# Driver.net
KiCad netlist of a schematic drawn in Altium Designer
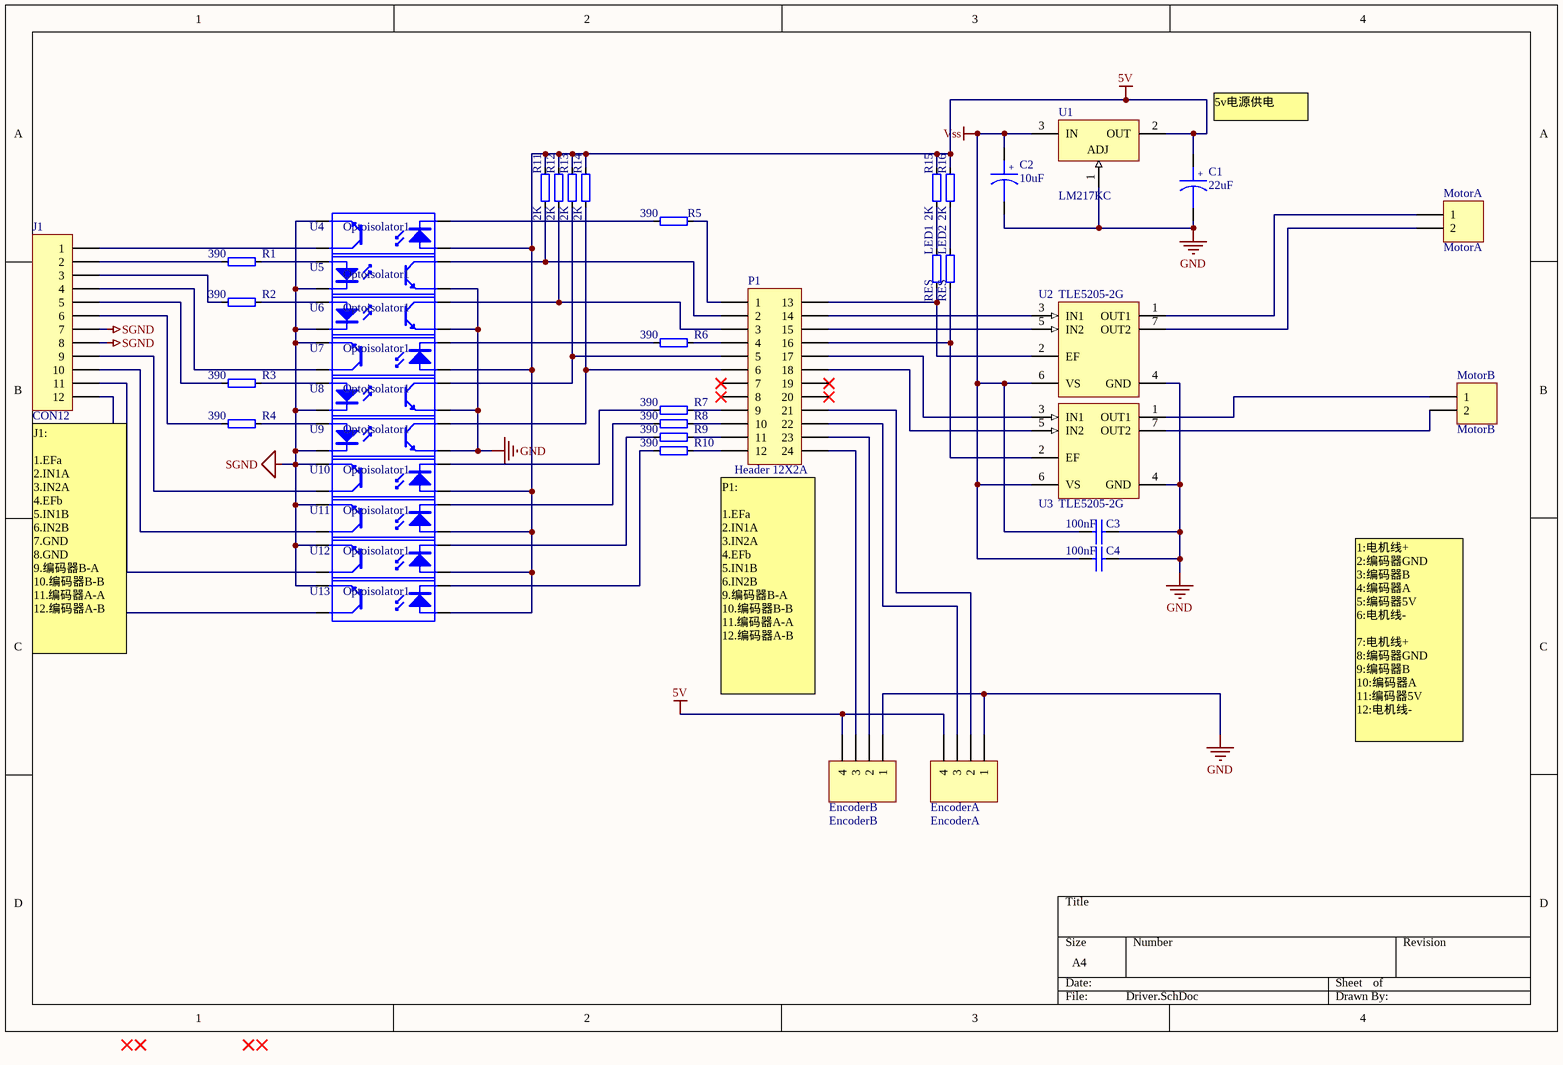
[diagram p0: Driver.SchDoc]

(export (version "E")
  (design (tool "Eeschema 10.0.6"))
  (components
    (comp (ref "C1")
      (value "22uF")
      (footprint "RB.2/.4")
      (description "Capacitor")
      (libsource (lib "电容") (part "电解电容"))
    )
    (comp (ref "C2")
      (value "10uF")
      (footprint "RB.2/.4")
      (description "Capacitor")
      (libsource (lib "电容") (part "电解电容"))
    )
    (comp (ref "C3")
      (value "100nF")
      (footprint "0805")
      (description "Capacitor")
      (libsource (lib "电容") (part "普通电容"))
    )
    (comp (ref "C4")
      (value "100nF")
      (footprint "0805")
      (description "Capacitor")
      (libsource (lib "电容") (part "普通电容"))
    )
    (comp (ref "EncoderA")
      (value "EncoderA")
      (footprint "SIP4-150")
      (description "Header, 4-Pin")
      (fields (field (name "PUBLISHER") "Altium Limited"))
      (libsource (lib "Miscellaneous Connectors") (part "Header 4"))
    )
    (comp (ref "EncoderB")
      (value "EncoderB")
      (footprint "SIP4-150")
      (description "Header, 4-Pin")
      (fields (field (name "PUBLISHER") "Altium Limited"))
      (libsource (lib "Miscellaneous Connectors") (part "Header 4"))
    )
    (comp (ref "J1")
      (value "CON12")
      (footprint "si12")
      (description "Connector")
      (libsource (lib "Miscellaneous Devices") (part "CON12"))
    )
    (comp (ref "LED1") (value "RES") (footprint "LED-0805") (libsource (lib "电阻") (part "RES")))
    (comp (ref "LED2") (value "RES") (footprint "LED-0805") (libsource (lib "电阻") (part "RES")))
    (comp (ref "MotorA")
      (value "MotorA")
      (footprint "SIP2-150")
      (description "Header, 2-Pin")
      (fields (field (name "PUBLISHER") "Altium Limited"))
      (libsource (lib "Miscellaneous Connectors") (part "Header 2"))
    )
    (comp (ref "MotorB")
      (value "MotorB")
      (footprint "SIP2-150")
      (description "Header, 2-Pin")
      (fields (field (name "PUBLISHER") "Altium Limited"))
      (libsource (lib "Miscellaneous Connectors") (part "Header 2"))
    )
    (comp (ref "P1")
      (value "Header 12X2A")
      (footprint "si2333")
      (description "Header, 12-Pin, Dual row")
      (fields (field (name "PUBLISHER") "Altium Limited"))
      (libsource (lib "Miscellaneous Connectors") (part "Header 12X2A"))
    )
    (comp (ref "R1") (value "390") (footprint "0603i") (libsource (lib "电阻") (part "RES")))
    (comp (ref "R2") (value "390") (footprint "0603i") (libsource (lib "电阻") (part "RES")))
    (comp (ref "R3") (value "390") (footprint "0603i") (libsource (lib "电阻") (part "RES")))
    (comp (ref "R4") (value "390") (footprint "0603i") (libsource (lib "电阻") (part "RES")))
    (comp (ref "R5") (value "390") (footprint "0603i") (libsource (lib "电阻") (part "RES")))
    (comp (ref "R6") (value "390") (footprint "0603i") (libsource (lib "电阻") (part "RES")))
    (comp (ref "R7") (value "390") (footprint "0603i") (libsource (lib "电阻") (part "RES")))
    (comp (ref "R8") (value "390") (footprint "0603i") (libsource (lib "电阻") (part "RES")))
    (comp (ref "R9") (value "390") (footprint "0603i") (libsource (lib "电阻") (part "RES")))
    (comp (ref "R10") (value "390") (footprint "0603i") (libsource (lib "电阻") (part "RES")))
    (comp (ref "R11") (value "2K") (footprint "0603i") (libsource (lib "电阻") (part "RES")))
    (comp (ref "R12") (value "2K") (footprint "0603i") (libsource (lib "电阻") (part "RES")))
    (comp (ref "R13") (value "2K") (footprint "0603i") (libsource (lib "电阻") (part "RES")))
    (comp (ref "R14") (value "2K") (footprint "0603i") (libsource (lib "电阻") (part "RES")))
    (comp (ref "R15") (value "2K") (footprint "0603i") (libsource (lib "电阻") (part "RES")))
    (comp (ref "R16") (value "2K") (footprint "0603i") (libsource (lib "电阻") (part "RES")))
    (comp (ref "U1")
      (value "LM217KC")
      (footprint "SOT223")
      (description "3-Terminal Adjustable Regulator")
      (fields (field (name "PUBLISHER") "Altium Limited"))
      (libsource (lib "TI Power Mgt Voltage Regulator") (part "LM217KC"))
    )
    (comp (ref "U2")
      (value "TLE5205-2G")
      (footprint "INF-PG-TO263-7-1_L")
      (description "5 A H-Bridge for DC-Motor Applications, 6 to 40 V, 220 mOhm RDS(on), PG-TO263-7-1, Reel, Green")
      (fields (field (name "MANUFACTURER") "Infineon"))
      (libsource (lib "TLE5205-2G") (part "TLE5205-2G"))
    )
    (comp (ref "U3")
      (value "TLE5205-2G")
      (footprint "INF-PG-TO263-7-1_L")
      (description "5 A H-Bridge for DC-Motor Applications, 6 to 40 V, 220 mOhm RDS(on), PG-TO263-7-1, Reel, Green")
      (fields (field (name "MANUFACTURER") "Infineon"))
      (libsource (lib "TLE5205-2G") (part "TLE5205-2G"))
    )
    (comp (ref "U4")
      (value "Optoisolator1")
      (footprint "TLP281")
      (description "4-Pin Phototransistor Optocoupler")
      (fields (field (name "PUBLISHER") "Altium Limited"))
      (libsource (lib "Miscellaneous Devices") (part "Optoisolator1"))
    )
    (comp (ref "U5")
      (value "Optoisolator1")
      (footprint "TLP281")
      (description "4-Pin Phototransistor Optocoupler")
      (fields (field (name "PUBLISHER") "Altium Limited"))
      (libsource (lib "Miscellaneous Devices") (part "Optoisolator1"))
    )
    (comp (ref "U6")
      (value "Optoisolator1")
      (footprint "TLP281")
      (description "4-Pin Phototransistor Optocoupler")
      (fields (field (name "PUBLISHER") "Altium Limited"))
      (libsource (lib "Miscellaneous Devices") (part "Optoisolator1"))
    )
    (comp (ref "U7")
      (value "Optoisolator1")
      (footprint "TLP281")
      (description "4-Pin Phototransistor Optocoupler")
      (fields (field (name "PUBLISHER") "Altium Limited"))
      (libsource (lib "Miscellaneous Devices") (part "Optoisolator1"))
    )
    (comp (ref "U8")
      (value "Optoisolator1")
      (footprint "TLP281")
      (description "4-Pin Phototransistor Optocoupler")
      (fields (field (name "PUBLISHER") "Altium Limited"))
      (libsource (lib "Miscellaneous Devices") (part "Optoisolator1"))
    )
    (comp (ref "U9")
      (value "Optoisolator1")
      (footprint "TLP281")
      (description "4-Pin Phototransistor Optocoupler")
      (fields (field (name "PUBLISHER") "Altium Limited"))
      (libsource (lib "Miscellaneous Devices") (part "Optoisolator1"))
    )
    (comp (ref "U10")
      (value "Optoisolator1")
      (footprint "TLP281")
      (description "4-Pin Phototransistor Optocoupler")
      (fields (field (name "PUBLISHER") "Altium Limited"))
      (libsource (lib "Miscellaneous Devices") (part "Optoisolator1"))
    )
    (comp (ref "U11")
      (value "Optoisolator1")
      (footprint "TLP281")
      (description "4-Pin Phototransistor Optocoupler")
      (fields (field (name "PUBLISHER") "Altium Limited"))
      (libsource (lib "Miscellaneous Devices") (part "Optoisolator1"))
    )
    (comp (ref "U12")
      (value "Optoisolator1")
      (footprint "TLP281")
      (description "4-Pin Phototransistor Optocoupler")
      (fields (field (name "PUBLISHER") "Altium Limited"))
      (libsource (lib "Miscellaneous Devices") (part "Optoisolator1"))
    )
    (comp (ref "U13")
      (value "Optoisolator1")
      (footprint "TLP281")
      (description "4-Pin Phototransistor Optocoupler")
      (fields (field (name "PUBLISHER") "Altium Limited"))
      (libsource (lib "Miscellaneous Devices") (part "Optoisolator1"))
    )
  )
  (nets
    (net (code "1") (name "5V") (class "Default")
      (node (ref "C1") (pin "1") (pinfunction "1_1") (pintype "passive"))
      (node (ref "EncoderA") (pin "4") (pinfunction "4_4") (pintype "passive"))
      (node (ref "EncoderB") (pin "4") (pinfunction "4_4") (pintype "passive"))
      (node (ref "R11") (pin "1") (pinfunction "1_1") (pintype "passive"))
      (node (ref "R12") (pin "1") (pinfunction "1_1") (pintype "passive"))
      (node (ref "R13") (pin "1") (pinfunction "1_1") (pintype "passive"))
      (node (ref "R14") (pin "1") (pinfunction "1_1") (pintype "passive"))
      (node (ref "R15") (pin "1") (pinfunction "1_1") (pintype "passive"))
      (node (ref "R16") (pin "1") (pinfunction "1_1") (pintype "passive"))
      (node (ref "U1") (pin "2") (pinfunction "OUT_2") (pintype "power_in"))
      (node (ref "U10") (pin "1") (pinfunction "A_1") (pintype "passive"))
      (node (ref "U11") (pin "1") (pinfunction "A_1") (pintype "passive"))
      (node (ref "U12") (pin "1") (pinfunction "A_1") (pintype "passive"))
      (node (ref "U13") (pin "1") (pinfunction "A_1") (pintype "passive"))
      (node (ref "U4") (pin "1") (pinfunction "A_1") (pintype "passive"))
      (node (ref "U7") (pin "1") (pinfunction "A_1") (pintype "passive"))
    )
    (net (code "2") (name "GND") (class "Default")
      (node (ref "C1") (pin "2") (pinfunction "2_2") (pintype "passive"))
      (node (ref "C2") (pin "2") (pinfunction "2_2") (pintype "passive"))
      (node (ref "C3") (pin "2") (pinfunction "2_2") (pintype "passive"))
      (node (ref "C4") (pin "2") (pinfunction "2_2") (pintype "passive"))
      (node (ref "EncoderA") (pin "1") (pinfunction "1_1") (pintype "passive"))
      (node (ref "EncoderB") (pin "1") (pinfunction "1_1") (pintype "passive"))
      (node (ref "U1") (pin "1") (pinfunction "ADJ_1") (pintype "input"))
      (node (ref "U2") (pin "4") (pinfunction "GND_4") (pintype "power_in"))
      (node (ref "U3") (pin "4") (pinfunction "GND_4") (pintype "power_in"))
      (node (ref "U5") (pin "3") (pinfunction "E_3") (pintype "passive"))
      (node (ref "U6") (pin "3") (pinfunction "E_3") (pintype "passive"))
      (node (ref "U8") (pin "3") (pinfunction "E_3") (pintype "passive"))
      (node (ref "U9") (pin "3") (pinfunction "E_3") (pintype "passive"))
    )
    (net (code "3") (name "Net-(EncoderA-Pad2)") (class "Default")
      (node (ref "EncoderA") (pin "2") (pinfunction "2_2") (pintype "passive"))
      (node (ref "P1") (pin "21") (pinfunction "21_21") (pintype "passive"))
    )
    (net (code "4") (name "Net-(EncoderA-Pad3)") (class "Default")
      (node (ref "EncoderA") (pin "3") (pinfunction "3_3") (pintype "passive"))
      (node (ref "P1") (pin "22") (pinfunction "22_22") (pintype "passive"))
    )
    (net (code "5") (name "Net-(EncoderB-Pad2)") (class "Default")
      (node (ref "EncoderB") (pin "2") (pinfunction "2_2") (pintype "passive"))
      (node (ref "P1") (pin "23") (pinfunction "23_23") (pintype "passive"))
    )
    (net (code "6") (name "Net-(EncoderB-Pad3)") (class "Default")
      (node (ref "EncoderB") (pin "3") (pinfunction "3_3") (pintype "passive"))
      (node (ref "P1") (pin "24") (pinfunction "24_24") (pintype "passive"))
    )
    (net (code "7") (name "Net-(J1-Pad2)") (class "Default")
      (node (ref "J1") (pin "2") (pinfunction "2_2") (pintype "passive"))
      (node (ref "R1") (pin "2") (pinfunction "2_2") (pintype "passive"))
    )
    (net (code "8") (name "Net-(J1-Pad3)") (class "Default")
      (node (ref "J1") (pin "3") (pinfunction "3_3") (pintype "passive"))
      (node (ref "R2") (pin "2") (pinfunction "2_2") (pintype "passive"))
    )
    (net (code "9") (name "Net-(J1-Pad5)") (class "Default")
      (node (ref "J1") (pin "5") (pinfunction "5_5") (pintype "passive"))
      (node (ref "R3") (pin "2") (pinfunction "2_2") (pintype "passive"))
    )
    (net (code "10") (name "Net-(J1-Pad6)") (class "Default")
      (node (ref "J1") (pin "6") (pinfunction "6_6") (pintype "passive"))
      (node (ref "R4") (pin "2") (pinfunction "2_2") (pintype "passive"))
    )
    (net (code "11") (name "Net-(LED1-Pad1)") (class "Default")
      (node (ref "LED1") (pin "1") (pinfunction "1_1") (pintype "passive"))
      (node (ref "R15") (pin "2") (pinfunction "2_2") (pintype "passive"))
    )
    (net (code "12") (name "Net-(LED2-Pad1)") (class "Default")
      (node (ref "LED2") (pin "1") (pinfunction "1_1") (pintype "passive"))
      (node (ref "R16") (pin "2") (pinfunction "2_2") (pintype "passive"))
    )
    (net (code "13") (name "Net-(P1-Pad1)") (class "Default")
      (node (ref "P1") (pin "1") (pinfunction "1_1") (pintype "passive"))
      (node (ref "R5") (pin "1") (pinfunction "1_1") (pintype "passive"))
    )
    (net (code "14") (name "Net-(P1-Pad4)") (class "Default")
      (node (ref "P1") (pin "4") (pinfunction "4_4") (pintype "passive"))
      (node (ref "R6") (pin "1") (pinfunction "1_1") (pintype "passive"))
    )
    (net (code "15") (name "Net-(P1-Pad9)") (class "Default")
      (node (ref "P1") (pin "9") (pinfunction "9_9") (pintype "passive"))
      (node (ref "R7") (pin "1") (pinfunction "1_1") (pintype "passive"))
    )
    (net (code "16") (name "Net-(P1-Pad10)") (class "Default")
      (node (ref "P1") (pin "10") (pinfunction "10_10") (pintype "passive"))
      (node (ref "R8") (pin "1") (pinfunction "1_1") (pintype "passive"))
    )
    (net (code "17") (name "Net-(P1-Pad11)") (class "Default")
      (node (ref "P1") (pin "11") (pinfunction "11_11") (pintype "passive"))
      (node (ref "R9") (pin "1") (pinfunction "1_1") (pintype "passive"))
    )
    (net (code "18") (name "Net-(P1-Pad12)") (class "Default")
      (node (ref "P1") (pin "12") (pinfunction "12_12") (pintype "passive"))
      (node (ref "R10") (pin "1") (pinfunction "1_1") (pintype "passive"))
    )
    (net (code "19") (name "Net-(U2-EF)") (class "Default")
      (node (ref "LED1") (pin "2") (pinfunction "2_2") (pintype "passive"))
      (node (ref "P1") (pin "13") (pinfunction "13_13") (pintype "passive"))
      (node (ref "U2") (pin "2") (pinfunction "EF_2") (pintype "open_collector"))
    )
    (net (code "20") (name "Net-(U2-IN1)") (class "Default")
      (node (ref "P1") (pin "14") (pinfunction "14_14") (pintype "passive"))
      (node (ref "U2") (pin "3") (pinfunction "IN1_3") (pintype "input"))
    )
    (net (code "21") (name "Net-(U2-IN2)") (class "Default")
      (node (ref "P1") (pin "15") (pinfunction "15_15") (pintype "passive"))
      (node (ref "U2") (pin "5") (pinfunction "IN2_5") (pintype "input"))
    )
    (net (code "22") (name "Net-(U2-OUT1)") (class "Default")
      (node (ref "MotorA") (pin "1") (pinfunction "1_1") (pintype "passive"))
      (node (ref "U2") (pin "1") (pinfunction "OUT1_1") (pintype "power_in"))
    )
    (net (code "23") (name "Net-(U2-OUT2)") (class "Default")
      (node (ref "MotorA") (pin "2") (pinfunction "2_2") (pintype "passive"))
      (node (ref "U2") (pin "7") (pinfunction "OUT2_7") (pintype "power_in"))
    )
    (net (code "24") (name "Net-(U3-EF)") (class "Default")
      (node (ref "LED2") (pin "2") (pinfunction "2_2") (pintype "passive"))
      (node (ref "P1") (pin "16") (pinfunction "16_16") (pintype "passive"))
      (node (ref "U3") (pin "2") (pinfunction "EF_2") (pintype "open_collector"))
    )
    (net (code "25") (name "Net-(U3-IN1)") (class "Default")
      (node (ref "P1") (pin "17") (pinfunction "17_17") (pintype "passive"))
      (node (ref "U3") (pin "3") (pinfunction "IN1_3") (pintype "input"))
    )
    (net (code "26") (name "Net-(U3-IN2)") (class "Default")
      (node (ref "P1") (pin "18") (pinfunction "18_18") (pintype "passive"))
      (node (ref "U3") (pin "5") (pinfunction "IN2_5") (pintype "input"))
    )
    (net (code "27") (name "Net-(U3-OUT1)") (class "Default")
      (node (ref "MotorB") (pin "1") (pinfunction "1_1") (pintype "passive"))
      (node (ref "U3") (pin "1") (pinfunction "OUT1_1") (pintype "power_in"))
    )
    (net (code "28") (name "Net-(U3-OUT2)") (class "Default")
      (node (ref "MotorB") (pin "2") (pinfunction "2_2") (pintype "passive"))
      (node (ref "U3") (pin "7") (pinfunction "OUT2_7") (pintype "power_in"))
    )
    (net (code "29") (name "Net-(U4-C)") (class "Default")
      (node (ref "J1") (pin "1") (pinfunction "1_1") (pintype "passive"))
      (node (ref "U4") (pin "4") (pinfunction "C_4") (pintype "passive"))
    )
    (net (code "30") (name "Net-(U4-K)") (class "Default")
      (node (ref "R5") (pin "2") (pinfunction "2_2") (pintype "passive"))
      (node (ref "U4") (pin "2") (pinfunction "K_2") (pintype "passive"))
    )
    (net (code "31") (name "Net-(U5-A)") (class "Default")
      (node (ref "R1") (pin "1") (pinfunction "1_1") (pintype "passive"))
      (node (ref "U5") (pin "1") (pinfunction "A_1") (pintype "passive"))
    )
    (net (code "32") (name "Net-(U5-C)") (class "Default")
      (node (ref "P1") (pin "2") (pinfunction "2_2") (pintype "passive"))
      (node (ref "R11") (pin "2") (pinfunction "2_2") (pintype "passive"))
      (node (ref "U5") (pin "4") (pinfunction "C_4") (pintype "passive"))
    )
    (net (code "33") (name "Net-(U6-A)") (class "Default")
      (node (ref "R2") (pin "1") (pinfunction "1_1") (pintype "passive"))
      (node (ref "U6") (pin "1") (pinfunction "A_1") (pintype "passive"))
    )
    (net (code "34") (name "Net-(U6-C)") (class "Default")
      (node (ref "P1") (pin "3") (pinfunction "3_3") (pintype "passive"))
      (node (ref "R12") (pin "2") (pinfunction "2_2") (pintype "passive"))
      (node (ref "U6") (pin "4") (pinfunction "C_4") (pintype "passive"))
    )
    (net (code "35") (name "Net-(U7-C)") (class "Default")
      (node (ref "J1") (pin "4") (pinfunction "4_4") (pintype "passive"))
      (node (ref "U7") (pin "4") (pinfunction "C_4") (pintype "passive"))
    )
    (net (code "36") (name "Net-(U7-K)") (class "Default")
      (node (ref "R6") (pin "2") (pinfunction "2_2") (pintype "passive"))
      (node (ref "U7") (pin "2") (pinfunction "K_2") (pintype "passive"))
    )
    (net (code "37") (name "Net-(U8-A)") (class "Default")
      (node (ref "R3") (pin "1") (pinfunction "1_1") (pintype "passive"))
      (node (ref "U8") (pin "1") (pinfunction "A_1") (pintype "passive"))
    )
    (net (code "38") (name "Net-(U8-C)") (class "Default")
      (node (ref "P1") (pin "5") (pinfunction "5_5") (pintype "passive"))
      (node (ref "R13") (pin "2") (pinfunction "2_2") (pintype "passive"))
      (node (ref "U8") (pin "4") (pinfunction "C_4") (pintype "passive"))
    )
    (net (code "39") (name "Net-(U9-A)") (class "Default")
      (node (ref "R4") (pin "1") (pinfunction "1_1") (pintype "passive"))
      (node (ref "U9") (pin "1") (pinfunction "A_1") (pintype "passive"))
    )
    (net (code "40") (name "Net-(U9-C)") (class "Default")
      (node (ref "P1") (pin "6") (pinfunction "6_6") (pintype "passive"))
      (node (ref "R14") (pin "2") (pinfunction "2_2") (pintype "passive"))
      (node (ref "U9") (pin "4") (pinfunction "C_4") (pintype "passive"))
    )
    (net (code "41") (name "Net-(U10-C)") (class "Default")
      (node (ref "J1") (pin "9") (pinfunction "9_9") (pintype "passive"))
      (node (ref "U10") (pin "4") (pinfunction "C_4") (pintype "passive"))
    )
    (net (code "42") (name "Net-(U10-K)") (class "Default")
      (node (ref "R7") (pin "2") (pinfunction "2_2") (pintype "passive"))
      (node (ref "U10") (pin "2") (pinfunction "K_2") (pintype "passive"))
    )
    (net (code "43") (name "Net-(U11-C)") (class "Default")
      (node (ref "J1") (pin "10") (pinfunction "10_10") (pintype "passive"))
      (node (ref "U11") (pin "4") (pinfunction "C_4") (pintype "passive"))
    )
    (net (code "44") (name "Net-(U11-K)") (class "Default")
      (node (ref "R8") (pin "2") (pinfunction "2_2") (pintype "passive"))
      (node (ref "U11") (pin "2") (pinfunction "K_2") (pintype "passive"))
    )
    (net (code "45") (name "Net-(U12-C)") (class "Default")
      (node (ref "J1") (pin "11") (pinfunction "11_11") (pintype "passive"))
      (node (ref "U12") (pin "4") (pinfunction "C_4") (pintype "passive"))
    )
    (net (code "46") (name "Net-(U12-K)") (class "Default")
      (node (ref "R9") (pin "2") (pinfunction "2_2") (pintype "passive"))
      (node (ref "U12") (pin "2") (pinfunction "K_2") (pintype "passive"))
    )
    (net (code "47") (name "Net-(U13-C)") (class "Default")
      (node (ref "J1") (pin "12") (pinfunction "12_12") (pintype "passive"))
      (node (ref "U13") (pin "4") (pinfunction "C_4") (pintype "passive"))
    )
    (net (code "48") (name "Net-(U13-K)") (class "Default")
      (node (ref "R10") (pin "2") (pinfunction "2_2") (pintype "passive"))
      (node (ref "U13") (pin "2") (pinfunction "K_2") (pintype "passive"))
    )
    (net (code "49") (name "SGND") (class "Default")
      (node (ref "J1") (pin "7") (pinfunction "7_7") (pintype "passive"))
      (node (ref "J1") (pin "8") (pinfunction "8_8") (pintype "passive"))
      (node (ref "U10") (pin "3") (pinfunction "E_3") (pintype "passive"))
      (node (ref "U11") (pin "3") (pinfunction "E_3") (pintype "passive"))
      (node (ref "U12") (pin "3") (pinfunction "E_3") (pintype "passive"))
      (node (ref "U13") (pin "3") (pinfunction "E_3") (pintype "passive"))
      (node (ref "U4") (pin "3") (pinfunction "E_3") (pintype "passive"))
      (node (ref "U5") (pin "2") (pinfunction "K_2") (pintype "passive"))
      (node (ref "U6") (pin "2") (pinfunction "K_2") (pintype "passive"))
      (node (ref "U7") (pin "3") (pinfunction "E_3") (pintype "passive"))
      (node (ref "U8") (pin "2") (pinfunction "K_2") (pintype "passive"))
      (node (ref "U9") (pin "2") (pinfunction "K_2") (pintype "passive"))
    )
    (net (code "50") (name "Vss") (class "Default")
      (node (ref "C2") (pin "1") (pinfunction "1_1") (pintype "passive"))
      (node (ref "C3") (pin "1") (pinfunction "1_1") (pintype "passive"))
      (node (ref "C4") (pin "1") (pinfunction "1_1") (pintype "passive"))
      (node (ref "U1") (pin "3") (pinfunction "IN_3") (pintype "power_in"))
      (node (ref "U2") (pin "6") (pinfunction "VS_6") (pintype "power_in"))
      (node (ref "U3") (pin "6") (pinfunction "VS_6") (pintype "power_in"))
    )
    (net (code "51") (name "unconnected-(P1-Pad7)") (class "Default")
      (node (ref "P1") (pin "7") (pinfunction "7_7") (pintype "passive+no_connect"))
    )
    (net (code "52") (name "unconnected-(P1-Pad8)") (class "Default")
      (node (ref "P1") (pin "8") (pinfunction "8_8") (pintype "passive+no_connect"))
    )
    (net (code "53") (name "unconnected-(P1-Pad19)") (class "Default")
      (node (ref "P1") (pin "19") (pinfunction "19_19") (pintype "passive+no_connect"))
    )
    (net (code "54") (name "unconnected-(P1-Pad20)") (class "Default")
      (node (ref "P1") (pin "20") (pinfunction "20_20") (pintype "passive+no_connect"))
    )
  )
)
